# carry-block.net
KiCad netlist of a schematic drawn in EAGLE
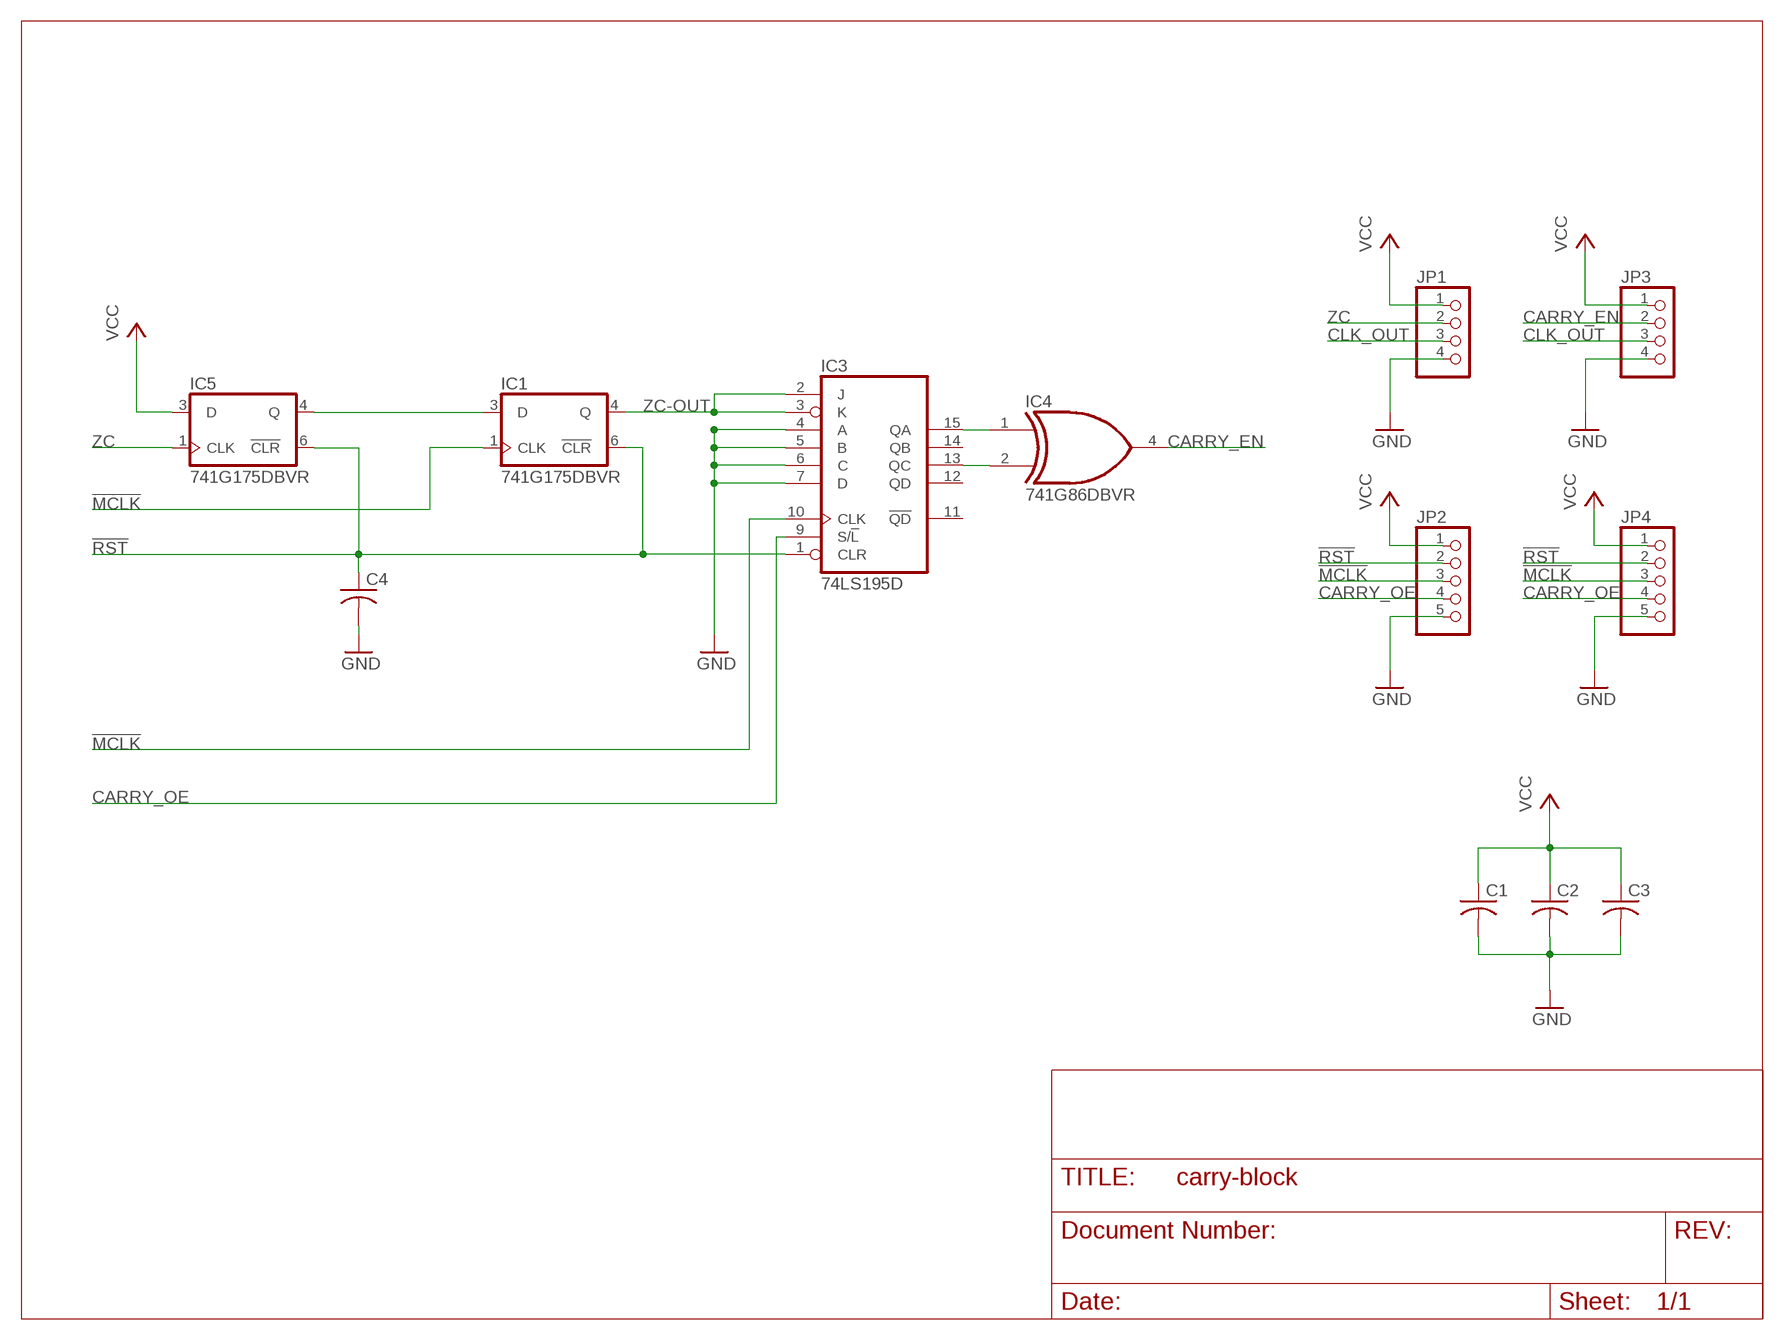
[diagram p0: schematic, sheet 1]

(export (version "E")
  (design (tool "Eeschema 10.0.6"))
  (components
    (comp (ref "C1")
      (value "C-USC0603K")
      (footprint "eagle-import:C0603K")
      (libsource (lib "eagle-import") (part "C-USC0603K"))
    )
    (comp (ref "C2")
      (value "C-USC0603K")
      (footprint "eagle-import:C0603K")
      (libsource (lib "eagle-import") (part "C-USC0603K"))
    )
    (comp (ref "C3")
      (value "C-USC0603K")
      (footprint "eagle-import:C0603K")
      (libsource (lib "eagle-import") (part "C-USC0603K"))
    )
    (comp (ref "C4")
      (value "C-USC0603K")
      (footprint "eagle-import:C0603K")
      (libsource (lib "eagle-import") (part "C-USC0603K"))
    )
    (comp (ref "IC1")
      (value "741G175DBVR")
      (footprint "eagle-import:DBV_R-PDSO-G6")
      (libsource (lib "eagle-import") (part "741G175"))
    )
    (comp (ref "IC3")
      (value "74LS195D")
      (footprint "eagle-import:SO16")
      (libsource (lib "eagle-import") (part "74195DLS"))
    )
    (comp (ref "IC4")
      (value "741G86DBVR")
      (footprint "eagle-import:SOT23-5")
      (libsource (lib "eagle-import") (part "741G86DBVAHC"))
    )
    (comp (ref "IC5")
      (value "741G175DBVR")
      (footprint "eagle-import:DBV_R-PDSO-G6")
      (libsource (lib "eagle-import") (part "741G175"))
    )
    (comp (ref "JP1")
      (value "PINHD-1X4")
      (footprint "eagle-import:1X04")
      (libsource (lib "eagle-import") (part "PINHD-1X4"))
    )
    (comp (ref "JP2")
      (value "PINHD-1X5")
      (footprint "eagle-import:1X05")
      (libsource (lib "eagle-import") (part "PINHD-1X5"))
    )
    (comp (ref "JP3")
      (value "PINHD-1X4")
      (footprint "eagle-import:1X04")
      (libsource (lib "eagle-import") (part "PINHD-1X4"))
    )
    (comp (ref "JP4")
      (value "PINHD-1X5")
      (footprint "eagle-import:1X05")
      (libsource (lib "eagle-import") (part "PINHD-1X5"))
    )
  )
  (nets
    (net (code "1") (name "/CARRY_EN") (class "Default")
      (node (ref "IC4") (pin "4") (pinfunction "O_4") (pintype "output"))
      (node (ref "JP3") (pin "2") (pinfunction "2_2") (pintype "passive"))
    )
    (net (code "2") (name "/CARRY_OE") (class "Default")
      (node (ref "IC3") (pin "9") (pinfunction "S/~{L}_9") (pintype "input"))
      (node (ref "JP2") (pin "4") (pinfunction "4_4") (pintype "passive"))
      (node (ref "JP4") (pin "4") (pinfunction "4_4") (pintype "passive"))
    )
    (net (code "3") (name "/CLK_OUT") (class "Default")
      (node (ref "JP1") (pin "3") (pinfunction "3_3") (pintype "passive"))
      (node (ref "JP3") (pin "3") (pinfunction "3_3") (pintype "passive"))
    )
    (net (code "4") (name "/ZC") (class "Default")
      (node (ref "IC5") (pin "1") (pinfunction "CLK_1") (pintype "input"))
      (node (ref "JP1") (pin "2") (pinfunction "2_2") (pintype "passive"))
    )
    (net (code "5") (name "/ZC-OUT") (class "Default")
      (node (ref "IC1") (pin "4") (pinfunction "Q_4") (pintype "output"))
      (node (ref "IC3") (pin "2") (pinfunction "J_2") (pintype "input"))
      (node (ref "IC3") (pin "3") (pinfunction "K_3") (pintype "input"))
    )
    (net (code "6") (name "/~{MCLK}") (class "Default")
      (node (ref "IC1") (pin "1") (pinfunction "CLK_1") (pintype "input"))
      (node (ref "IC3") (pin "10") (pinfunction "CLK_10") (pintype "input"))
      (node (ref "JP2") (pin "3") (pinfunction "3_3") (pintype "passive"))
      (node (ref "JP4") (pin "3") (pinfunction "3_3") (pintype "passive"))
    )
    (net (code "7") (name "/~{RST}") (class "Default")
      (node (ref "C4") (pin "1") (pinfunction "1_1") (pintype "passive"))
      (node (ref "IC1") (pin "6") (pinfunction "~{CLR}_6") (pintype "input"))
      (node (ref "IC3") (pin "1") (pinfunction "CLR_1") (pintype "input"))
      (node (ref "IC5") (pin "6") (pinfunction "~{CLR}_6") (pintype "input"))
      (node (ref "JP2") (pin "2") (pinfunction "2_2") (pintype "passive"))
      (node (ref "JP4") (pin "2") (pinfunction "2_2") (pintype "passive"))
    )
    (net (code "8") (name "GND") (class "Default")
      (node (ref "C1") (pin "2") (pinfunction "2_2") (pintype "passive"))
      (node (ref "C2") (pin "2") (pinfunction "2_2") (pintype "passive"))
      (node (ref "C3") (pin "2") (pinfunction "2_2") (pintype "passive"))
      (node (ref "C4") (pin "2") (pinfunction "2_2") (pintype "passive"))
      (node (ref "IC3") (pin "4") (pinfunction "A_4") (pintype "input"))
      (node (ref "IC3") (pin "5") (pinfunction "B_5") (pintype "input"))
      (node (ref "IC3") (pin "6") (pinfunction "C_6") (pintype "input"))
      (node (ref "IC3") (pin "7") (pinfunction "D_7") (pintype "input"))
      (node (ref "JP1") (pin "4") (pinfunction "4_4") (pintype "passive"))
      (node (ref "JP2") (pin "5") (pinfunction "5_5") (pintype "passive"))
      (node (ref "JP3") (pin "4") (pinfunction "4_4") (pintype "passive"))
      (node (ref "JP4") (pin "5") (pinfunction "5_5") (pintype "passive"))
    )
    (net (code "9") (name "Net-(IC1A-D)") (class "Default")
      (node (ref "IC1") (pin "3") (pinfunction "D_3") (pintype "input"))
      (node (ref "IC5") (pin "4") (pinfunction "Q_4") (pintype "output"))
    )
    (net (code "10") (name "Net-(IC3A-QA)") (class "Default")
      (node (ref "IC3") (pin "15") (pinfunction "QA_15") (pintype "output"))
      (node (ref "IC4") (pin "1") (pinfunction "I0_1") (pintype "input"))
    )
    (net (code "11") (name "Net-(IC3A-QC)") (class "Default")
      (node (ref "IC3") (pin "13") (pinfunction "QC_13") (pintype "output"))
      (node (ref "IC4") (pin "2") (pinfunction "I1_2") (pintype "input"))
    )
    (net (code "12") (name "VCC") (class "Default")
      (node (ref "C1") (pin "1") (pinfunction "1_1") (pintype "passive"))
      (node (ref "C2") (pin "1") (pinfunction "1_1") (pintype "passive"))
      (node (ref "C3") (pin "1") (pinfunction "1_1") (pintype "passive"))
      (node (ref "IC5") (pin "3") (pinfunction "D_3") (pintype "input"))
      (node (ref "JP1") (pin "1") (pinfunction "1_1") (pintype "passive"))
      (node (ref "JP2") (pin "1") (pinfunction "1_1") (pintype "passive"))
      (node (ref "JP3") (pin "1") (pinfunction "1_1") (pintype "passive"))
      (node (ref "JP4") (pin "1") (pinfunction "1_1") (pintype "passive"))
    )
    (net (code "13") (name "unconnected-(IC3A-QB-Pad14)") (class "Default")
      (node (ref "IC3") (pin "14") (pinfunction "QB_14") (pintype "output"))
    )
    (net (code "14") (name "unconnected-(IC3A-QD-Pad12)") (class "Default")
      (node (ref "IC3") (pin "12") (pinfunction "QD_12") (pintype "output"))
    )
    (net (code "15") (name "unconnected-(IC3A-~{QD}-Pad11)") (class "Default")
      (node (ref "IC3") (pin "11") (pinfunction "~{QD}_11") (pintype "output"))
    )
  )
)
